# Esquem_tico.net
KiCad netlist of a schematic drawn in EAGLE
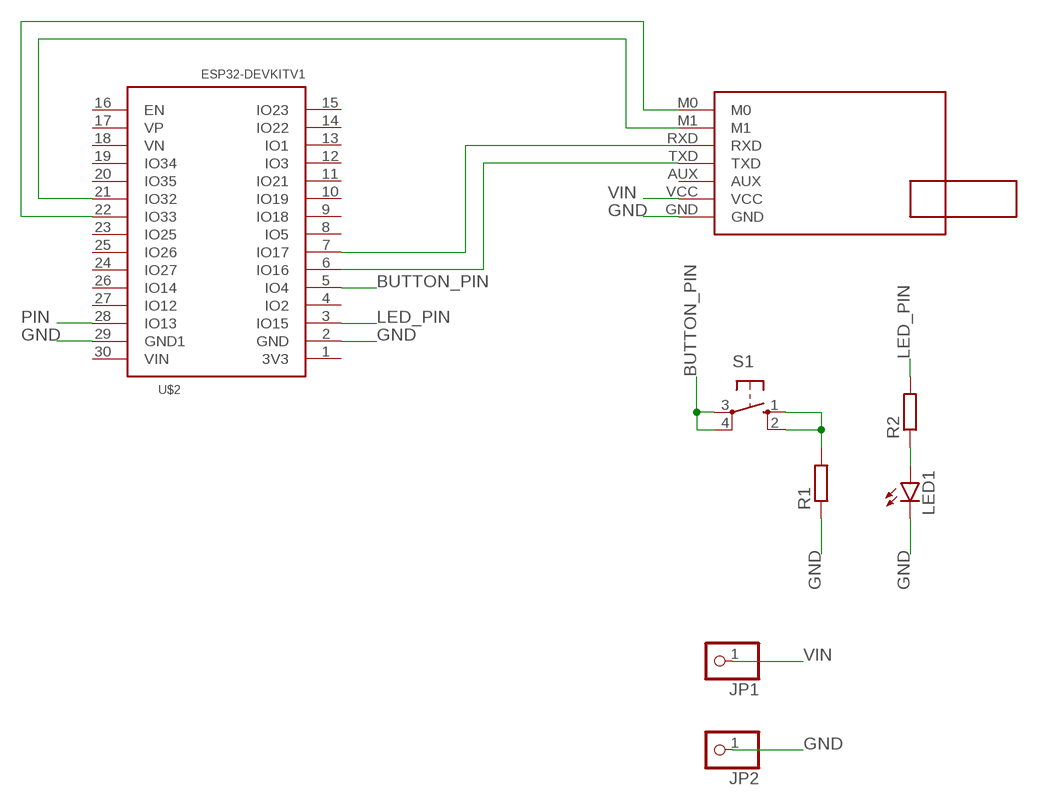
[diagram p0: schematic, sheet 1]

(export (version "E")
  (design (tool "Eeschema 10.0.6"))
  (components
    (comp (ref "JP1")
      (value "PINHD-1X1")
      (footprint "eagle-import:1X01")
      (libsource (lib "eagle-import") (part "PINHD-1X1"))
    )
    (comp (ref "JP2")
      (value "PINHD-1X1")
      (footprint "eagle-import:1X01")
      (libsource (lib "eagle-import") (part "PINHD-1X1"))
    )
    (comp (ref "LED1")
      (value "LED5MM")
      (footprint "eagle-import:LED5MM")
      (libsource (lib "eagle-import") (part "LED5MM"))
    )
    (comp (ref "R1")
      (value "R-EU_0207/10")
      (footprint "eagle-import:0207_10")
      (libsource (lib "eagle-import") (part "R-EU_0207/10"))
    )
    (comp (ref "R2")
      (value "R-EU_0207/10")
      (footprint "eagle-import:0207_10")
      (libsource (lib "eagle-import") (part "R-EU_0207/10"))
    )
    (comp (ref "S1")
      (value "10-XX")
      (footprint "eagle-import:B3F-10XX")
      (fields (field (name "MPN") "B3F-1000"))
      (libsource (lib "eagle-import") (part "10-XX"))
    )
    (comp (ref "U$1")
      (value "E22-400T30D")
      (footprint "eagle-import:E22-400T30D_FOOTPRINT")
      (libsource (lib "eagle-import") (part "E22-400T30D"))
    )
    (comp (ref "U$2")
      (value "ESP32DEVKITV1")
      (footprint "eagle-import:ESP32-DEVKITV1")
      (libsource (lib "eagle-import") (part "ESP32DEVKITV1"))
    )
  )
  (nets
    (net (code "1") (name "/BUTTON_PIN") (class "Default")
      (node (ref "S1") (pin "3") (pinfunction "P_3") (pintype "passive"))
      (node (ref "S1") (pin "4") (pinfunction "P1_4") (pintype "passive"))
      (node (ref "U$2") (pin "5") (pinfunction "IO4_5") (pintype "bidirectional"))
    )
    (net (code "2") (name "/GND") (class "Default")
      (node (ref "JP2") (pin "1") (pinfunction "1_1") (pintype "passive"))
      (node (ref "LED1") (pin "K") (pinfunction "C_K") (pintype "passive"))
      (node (ref "R1") (pin "1") (pinfunction "1_1") (pintype "passive"))
      (node (ref "U$1") (pin "GND") (pinfunction "GND_GND") (pintype "bidirectional"))
      (node (ref "U$2") (pin "2") (pinfunction "GND_2") (pintype "bidirectional"))
      (node (ref "U$2") (pin "29") (pinfunction "GND1_29") (pintype "bidirectional"))
    )
    (net (code "3") (name "/LED_PIN") (class "Default")
      (node (ref "R2") (pin "2") (pinfunction "2_2") (pintype "passive"))
      (node (ref "U$2") (pin "3") (pinfunction "IO15_3") (pintype "bidirectional"))
    )
    (net (code "4") (name "/PIN") (class "Default")
      (node (ref "U$2") (pin "28") (pinfunction "IO13_28") (pintype "bidirectional"))
    )
    (net (code "5") (name "/VIN") (class "Default")
      (node (ref "JP1") (pin "1") (pinfunction "1_1") (pintype "passive"))
      (node (ref "U$1") (pin "VCC") (pinfunction "VCC_VCC") (pintype "bidirectional"))
    )
    (net (code "6") (name "Net-(LED1-PadA)") (class "Default")
      (node (ref "LED1") (pin "A") (pinfunction "A_A") (pintype "passive"))
      (node (ref "R2") (pin "1") (pinfunction "1_1") (pintype "passive"))
    )
    (net (code "7") (name "Net-(S1-S)") (class "Default")
      (node (ref "R1") (pin "2") (pinfunction "2_2") (pintype "passive"))
      (node (ref "S1") (pin "1") (pinfunction "S_1") (pintype "passive"))
      (node (ref "S1") (pin "2") (pinfunction "S1_2") (pintype "passive"))
    )
    (net (code "8") (name "Net-(U$2-IO16)") (class "Default")
      (node (ref "U$1") (pin "TXD") (pinfunction "TXD_TXD") (pintype "bidirectional"))
      (node (ref "U$2") (pin "6") (pinfunction "IO16_6") (pintype "bidirectional"))
    )
    (net (code "9") (name "Net-(U$2-IO17)") (class "Default")
      (node (ref "U$1") (pin "RXD") (pinfunction "RXD_RXD") (pintype "bidirectional"))
      (node (ref "U$2") (pin "7") (pinfunction "IO17_7") (pintype "bidirectional"))
    )
    (net (code "10") (name "Net-(U$2-IO32)") (class "Default")
      (node (ref "U$1") (pin "M1") (pinfunction "M1_M1") (pintype "bidirectional"))
      (node (ref "U$2") (pin "21") (pinfunction "IO32_21") (pintype "bidirectional"))
    )
    (net (code "11") (name "Net-(U$2-IO33)") (class "Default")
      (node (ref "U$1") (pin "M0") (pinfunction "M0_M0") (pintype "bidirectional"))
      (node (ref "U$2") (pin "22") (pinfunction "IO33_22") (pintype "bidirectional"))
    )
    (net (code "12") (name "unconnected-(U$1-PadAUX)") (class "Default")
      (node (ref "U$1") (pin "AUX") (pinfunction "AUX_AUX") (pintype "bidirectional"))
    )
    (net (code "13") (name "unconnected-(U$2-3V3-Pad1)") (class "Default")
      (node (ref "U$2") (pin "1") (pinfunction "3V3_1") (pintype "bidirectional"))
    )
    (net (code "14") (name "unconnected-(U$2-EN-Pad16)") (class "Default")
      (node (ref "U$2") (pin "16") (pinfunction "EN_16") (pintype "bidirectional"))
    )
    (net (code "15") (name "unconnected-(U$2-IO1-Pad13)") (class "Default")
      (node (ref "U$2") (pin "13") (pinfunction "IO1_13") (pintype "bidirectional"))
    )
    (net (code "16") (name "unconnected-(U$2-IO2-Pad4)") (class "Default")
      (node (ref "U$2") (pin "4") (pinfunction "IO2_4") (pintype "bidirectional"))
    )
    (net (code "17") (name "unconnected-(U$2-IO3-Pad12)") (class "Default")
      (node (ref "U$2") (pin "12") (pinfunction "IO3_12") (pintype "bidirectional"))
    )
    (net (code "18") (name "unconnected-(U$2-IO5-Pad8)") (class "Default")
      (node (ref "U$2") (pin "8") (pinfunction "IO5_8") (pintype "bidirectional"))
    )
    (net (code "19") (name "unconnected-(U$2-IO12-Pad27)") (class "Default")
      (node (ref "U$2") (pin "27") (pinfunction "IO12_27") (pintype "bidirectional"))
    )
    (net (code "20") (name "unconnected-(U$2-IO14-Pad26)") (class "Default")
      (node (ref "U$2") (pin "26") (pinfunction "IO14_26") (pintype "bidirectional"))
    )
    (net (code "21") (name "unconnected-(U$2-IO18-Pad9)") (class "Default")
      (node (ref "U$2") (pin "9") (pinfunction "IO18_9") (pintype "bidirectional"))
    )
    (net (code "22") (name "unconnected-(U$2-IO19-Pad10)") (class "Default")
      (node (ref "U$2") (pin "10") (pinfunction "IO19_10") (pintype "bidirectional"))
    )
    (net (code "23") (name "unconnected-(U$2-IO21-Pad11)") (class "Default")
      (node (ref "U$2") (pin "11") (pinfunction "IO21_11") (pintype "bidirectional"))
    )
    (net (code "24") (name "unconnected-(U$2-IO22-Pad14)") (class "Default")
      (node (ref "U$2") (pin "14") (pinfunction "IO22_14") (pintype "bidirectional"))
    )
    (net (code "25") (name "unconnected-(U$2-IO23-Pad15)") (class "Default")
      (node (ref "U$2") (pin "15") (pinfunction "IO23_15") (pintype "bidirectional"))
    )
    (net (code "26") (name "unconnected-(U$2-IO25-Pad23)") (class "Default")
      (node (ref "U$2") (pin "23") (pinfunction "IO25_23") (pintype "bidirectional"))
    )
    (net (code "27") (name "unconnected-(U$2-IO26-Pad25)") (class "Default")
      (node (ref "U$2") (pin "25") (pinfunction "IO26_25") (pintype "bidirectional"))
    )
    (net (code "28") (name "unconnected-(U$2-IO27-Pad24)") (class "Default")
      (node (ref "U$2") (pin "24") (pinfunction "IO27_24") (pintype "bidirectional"))
    )
    (net (code "29") (name "unconnected-(U$2-IO34-Pad19)") (class "Default")
      (node (ref "U$2") (pin "19") (pinfunction "IO34_19") (pintype "bidirectional"))
    )
    (net (code "30") (name "unconnected-(U$2-IO35-Pad20)") (class "Default")
      (node (ref "U$2") (pin "20") (pinfunction "IO35_20") (pintype "bidirectional"))
    )
    (net (code "31") (name "unconnected-(U$2-VIN-Pad30)") (class "Default")
      (node (ref "U$2") (pin "30") (pinfunction "VIN_30") (pintype "bidirectional"))
    )
    (net (code "32") (name "unconnected-(U$2-VN-Pad18)") (class "Default")
      (node (ref "U$2") (pin "18") (pinfunction "VN_18") (pintype "bidirectional"))
    )
    (net (code "33") (name "unconnected-(U$2-VP-Pad17)") (class "Default")
      (node (ref "U$2") (pin "17") (pinfunction "VP_17") (pintype "bidirectional"))
    )
  )
)
